# 1_P1.net
KiCad netlist of a schematic drawn in Altium Designer
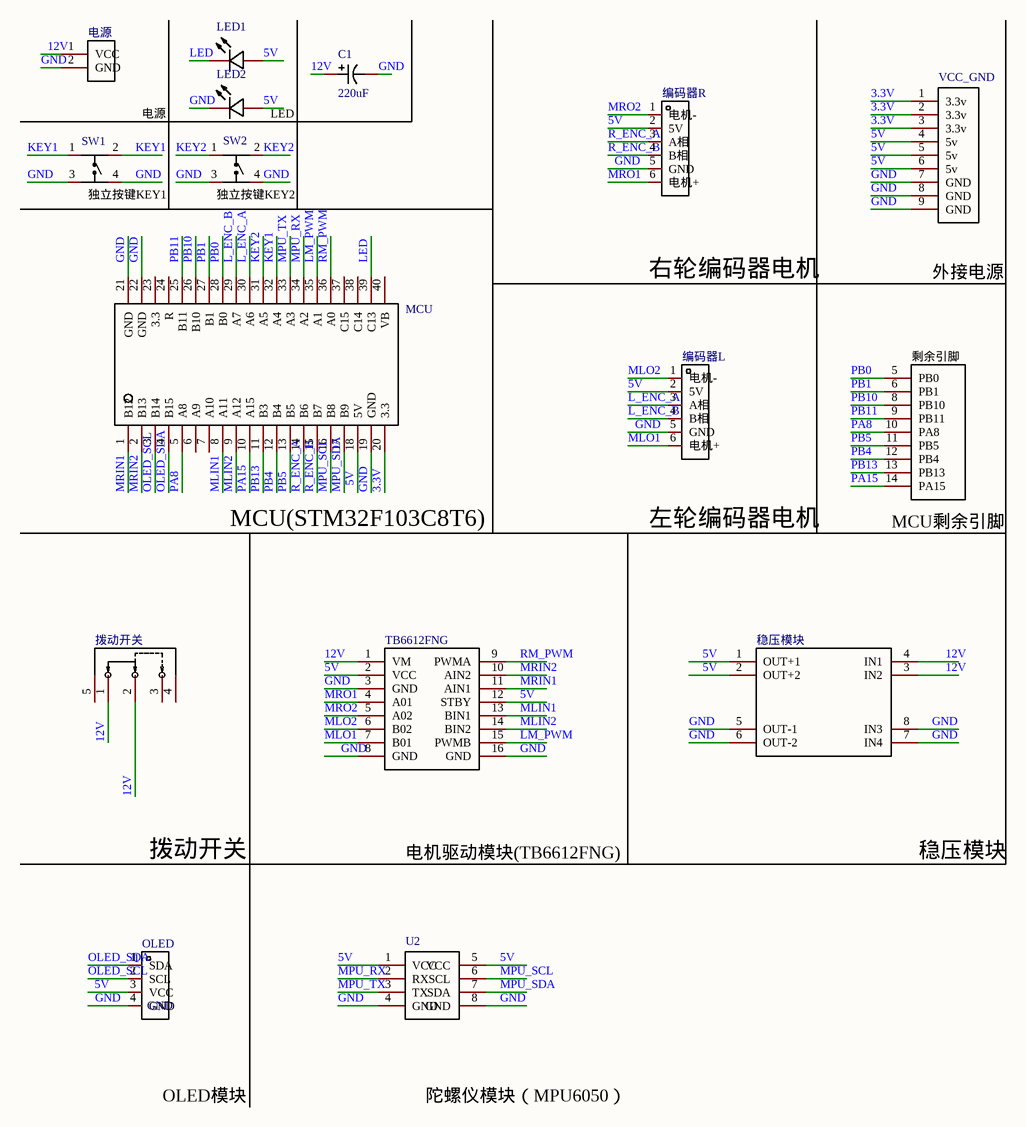
[diagram p0: 1_P1.schdoc]

(export (version "E")
  (design (tool "Eeschema 10.0.6"))
  (components
    (comp (ref "C1")
      (value "220uF")
      (description "容值:220uF;额定电压:25V;电容体直径:-;电容体长度:-;脚间距:3.5mm;纹波电流:-;等效串联电阻:-;工作寿命:-;")
      (fields (field (name "MANUFACTURER") "PANASONIC(松下)") (field (name "MANUFACTURER PART") "EEUFM1E221"))
      (libsource (lib "altium-import") (part "root_0_U1_"))
    )
    (comp (ref "LED1")
      (value "HL-PST-1608U51GC")
      (description "发光颜色:翠绿;透镜颜色:无色透明;主波长:-;色温:-;测试电流:10mA;功率:66mW;发光角度:130°;安装方式:正贴;工作温度:-40~+85;")
      (fields (field (name "MANUFACTURER") "HONGLITRONIC(鸿利光电)"))
      (libsource (lib "altium-import") (part "root_0_HL-PST-1608U51GC_"))
    )
    (comp (ref "LED2")
      (value "HL-PST-1608U51GC")
      (description "发光颜色:翠绿;透镜颜色:无色透明;主波长:-;色温:-;测试电流:10mA;功率:66mW;发光角度:130°;安装方式:正贴;工作温度:-40~+85;")
      (fields (field (name "MANUFACTURER") "HONGLITRONIC(鸿利光电)"))
      (libsource (lib "altium-import") (part "root_0_HL-PST-1608U51GC_"))
    )
    (comp (ref "MCU")
      (value "Stm32f103c8t6")
      (description "模块")
      (libsource (lib "altium-import") (part "root_1_Stm32f103c8t6_"))
    )
    (comp (ref "OLED")
      (value "OLED（4Pin）")
      (fields (field (name "NAME") "GND") (field (name "NUMBER") "1"))
      (libsource (lib "altium-import") (part "root_0_OLED（4Pin）_"))
    )
    (comp (ref "SW1")
      (value "KH-6X6X5H-TJ")
      (fields (field (name "MANUFACTURER") "kinghelm(金航标)"))
      (libsource (lib "altium-import") (part "root_0_KH-6X6X5H-TJ_"))
    )
    (comp (ref "SW2")
      (value "KH-6X6X5H-TJ")
      (fields (field (name "MANUFACTURER") "kinghelm(金航标)"))
      (libsource (lib "altium-import") (part "root_0_KH-6X6X5H-TJ_"))
    )
    (comp (ref "TB6612FNG")
      (value "TB6612fng（16PIN）")
      (libsource (lib "altium-import") (part "root_0_TB6612fng（16PIN）_"))
    )
    (comp (ref "U1") (value "MCU剩余引脚") (libsource (lib "altium-import") (part "root_0_MCU剩余引脚_")))
    (comp (ref "U2") (value "MPU6050_JY-61") (libsource (lib "altium-import") (part "root_0_MPU6050_JY-61_")))
    (comp (ref "VCC_GND") (value "VCC_GND") (libsource (lib "altium-import") (part "root_0_VCC_GND_")))
    (comp (ref "拨动开关")
      (value "拨动开关（3PIN）")
      (fields (field (name "MANUFACTURER") "SHOU HAN(首韩)") (field (name "MANUFACTURER PART") "SK12D07VG4"))
      (libsource (lib "altium-import") (part "root_0_拨动开关（3PIN）_"))
    )
    (comp (ref "电源") (value "电源") (libsource (lib "altium-import") (part "root_0_电源_")))
    (comp (ref "稳压模块")
      (value "稳压模块（-5v）")
      (description "模块")
      (libsource (lib "altium-import") (part "root_0_稳压模块（-5v）_"))
    )
    (comp (ref "编码器L")
      (value "A2547WR-6P")
      (description "参考系列:-;间距:2.54mm;插针结构:1x6P;排数:1;每排PIN数:6;行距:-;安装方式:-;触头材质:黄铜;")
      (fields (field (name "MANUFACTURER") "CJT(长江连接器)"))
      (libsource (lib "altium-import") (part "root_0_A2547WR-6P_"))
    )
    (comp (ref "编码器R")
      (value "A2547WR-6P")
      (description "参考系列:-;间距:2.54mm;插针结构:1x6P;排数:1;每排PIN数:6;行距:-;安装方式:-;触头材质:黄铜;")
      (fields (field (name "MANUFACTURER") "CJT(长江连接器)"))
      (libsource (lib "altium-import") (part "root_0_A2547WR-6P_"))
    )
  )
  (nets
    (net (code "1") (name "/3.3V") (class "Default")
      (node (ref "MCU") (pin "20") (pinfunction "3.3_20") (pintype "passive"))
      (node (ref "VCC_GND") (pin "1") (pinfunction "3.3v_1") (pintype "passive"))
      (node (ref "VCC_GND") (pin "2") (pinfunction "3.3v_2") (pintype "passive"))
      (node (ref "VCC_GND") (pin "3") (pinfunction "3.3v_3") (pintype "passive"))
    )
    (net (code "2") (name "/5V") (class "Default")
      (node (ref "LED1") (pin "1") (pinfunction "A_1") (pintype "passive"))
      (node (ref "LED2") (pin "1") (pinfunction "A_1") (pintype "passive"))
      (node (ref "MCU") (pin "18") (pinfunction "5V_18") (pintype "passive"))
      (node (ref "OLED") (pin "3") (pinfunction "VCC_3") (pintype "passive"))
      (node (ref "TB6612FNG") (pin "12") (pinfunction "STBY_12") (pintype "passive"))
      (node (ref "TB6612FNG") (pin "2") (pinfunction "VCC_2") (pintype "passive"))
      (node (ref "U2") (pin "1") (pinfunction "VCC_1") (pintype "passive"))
      (node (ref "U2") (pin "5") (pinfunction "VCC_5") (pintype "passive"))
      (node (ref "VCC_GND") (pin "4") (pinfunction "5v_4") (pintype "passive"))
      (node (ref "VCC_GND") (pin "5") (pinfunction "5v_5") (pintype "passive"))
      (node (ref "VCC_GND") (pin "6") (pinfunction "5v_6") (pintype "passive"))
      (node (ref "稳压模块") (pin "1") (pinfunction "OUT+1_1") (pintype "passive"))
      (node (ref "稳压模块") (pin "2") (pinfunction "OUT+2_2") (pintype "passive"))
      (node (ref "编码器L") (pin "2") (pinfunction "5V_2") (pintype "passive"))
      (node (ref "编码器R") (pin "2") (pinfunction "5V_2") (pintype "passive"))
    )
    (net (code "3") (name "/12V") (class "Default")
      (node (ref "C1") (pin "1") (pinfunction "1_1") (pintype "passive"))
      (node (ref "TB6612FNG") (pin "1") (pinfunction "VM_1") (pintype "passive"))
      (node (ref "拨动开关") (pin "1") (pinfunction "1_1") (pintype "passive"))
      (node (ref "拨动开关") (pin "2") (pinfunction "2_2") (pintype "passive"))
      (node (ref "电源") (pin "1") (pinfunction "VCC_1") (pintype "passive"))
      (node (ref "稳压模块") (pin "3") (pinfunction "IN2_3") (pintype "passive"))
      (node (ref "稳压模块") (pin "4") (pinfunction "IN1_4") (pintype "passive"))
    )
    (net (code "5") (name "/GND") (class "Default")
      (node (ref "C1") (pin "2") (pinfunction "2_2") (pintype "passive"))
      (node (ref "LED2") (pin "2") (pinfunction "K_2") (pintype "passive"))
      (node (ref "MCU") (pin "19") (pinfunction "GND_19") (pintype "passive"))
      (node (ref "MCU") (pin "21") (pinfunction "GND_21") (pintype "passive"))
      (node (ref "MCU") (pin "22") (pinfunction "GND_22") (pintype "passive"))
      (node (ref "OLED") (pin "4") (pinfunction "GND_4") (pintype "passive"))
      (node (ref "SW1") (pin "3") (pinfunction "3_3") (pintype "passive"))
      (node (ref "SW1") (pin "4") (pinfunction "4_4") (pintype "passive"))
      (node (ref "SW2") (pin "3") (pinfunction "3_3") (pintype "passive"))
      (node (ref "SW2") (pin "4") (pinfunction "4_4") (pintype "passive"))
      (node (ref "TB6612FNG") (pin "16") (pinfunction "GND_16") (pintype "passive"))
      (node (ref "TB6612FNG") (pin "3") (pinfunction "GND_3") (pintype "passive"))
      (node (ref "TB6612FNG") (pin "8") (pinfunction "GND_8") (pintype "passive"))
      (node (ref "U2") (pin "4") (pinfunction "GND_4") (pintype "passive"))
      (node (ref "U2") (pin "8") (pinfunction "GND_8") (pintype "passive"))
      (node (ref "VCC_GND") (pin "7") (pinfunction "GND_7") (pintype "passive"))
      (node (ref "VCC_GND") (pin "8") (pinfunction "GND_8") (pintype "passive"))
      (node (ref "VCC_GND") (pin "9") (pinfunction "GND_9") (pintype "passive"))
      (node (ref "电源") (pin "2") (pinfunction "GND_2") (pintype "passive"))
      (node (ref "稳压模块") (pin "5") (pinfunction "OUT-1_5") (pintype "passive"))
      (node (ref "稳压模块") (pin "6") (pinfunction "OUT-2_6") (pintype "passive"))
      (node (ref "稳压模块") (pin "7") (pinfunction "IN4_7") (pintype "passive"))
      (node (ref "稳压模块") (pin "8") (pinfunction "IN3_8") (pintype "passive"))
      (node (ref "编码器L") (pin "5") (pinfunction "GND_5") (pintype "passive"))
      (node (ref "编码器R") (pin "5") (pinfunction "GND_5") (pintype "passive"))
    )
    (net (code "6") (name "/KEY1") (class "Default")
      (node (ref "MCU") (pin "32") (pinfunction "A4_32") (pintype "passive"))
      (node (ref "SW1") (pin "1") (pinfunction "1_1") (pintype "passive"))
      (node (ref "SW1") (pin "2") (pinfunction "2_2") (pintype "passive"))
    )
    (net (code "7") (name "/KEY2") (class "Default")
      (node (ref "MCU") (pin "31") (pinfunction "A5_31") (pintype "passive"))
      (node (ref "SW2") (pin "1") (pinfunction "1_1") (pintype "passive"))
      (node (ref "SW2") (pin "2") (pinfunction "2_2") (pintype "passive"))
    )
    (net (code "8") (name "/LED") (class "Default")
      (node (ref "LED1") (pin "2") (pinfunction "K_2") (pintype "passive"))
      (node (ref "MCU") (pin "39") (pinfunction "C13_39") (pintype "passive"))
    )
    (net (code "9") (name "/LM_PWM") (class "Default")
      (node (ref "MCU") (pin "35") (pinfunction "A1_35") (pintype "passive"))
      (node (ref "TB6612FNG") (pin "15") (pinfunction "PWMB_15") (pintype "passive"))
    )
    (net (code "10") (name "/L_ENC_A") (class "Default")
      (node (ref "MCU") (pin "30") (pinfunction "A6_30") (pintype "passive"))
      (node (ref "编码器L") (pin "3") (pinfunction "A相_3") (pintype "passive"))
    )
    (net (code "11") (name "/L_ENC_B") (class "Default")
      (node (ref "MCU") (pin "29") (pinfunction "A7_29") (pintype "passive"))
      (node (ref "编码器L") (pin "4") (pinfunction "B相_4") (pintype "passive"))
    )
    (net (code "12") (name "/MLIN1") (class "Default")
      (node (ref "MCU") (pin "8") (pinfunction "A11_8") (pintype "passive"))
      (node (ref "TB6612FNG") (pin "13") (pinfunction "BIN1_13") (pintype "passive"))
    )
    (net (code "13") (name "/MLIN2") (class "Default")
      (node (ref "MCU") (pin "9") (pinfunction "A12_9") (pintype "passive"))
      (node (ref "TB6612FNG") (pin "14") (pinfunction "BIN2_14") (pintype "passive"))
    )
    (net (code "14") (name "/MLO1") (class "Default")
      (node (ref "TB6612FNG") (pin "7") (pinfunction "B01_7") (pintype "passive"))
      (node (ref "编码器L") (pin "6") (pinfunction "电机+_6") (pintype "passive"))
    )
    (net (code "15") (name "/MLO2") (class "Default")
      (node (ref "TB6612FNG") (pin "6") (pinfunction "B02_6") (pintype "passive"))
      (node (ref "编码器L") (pin "1") (pinfunction "电机-_1") (pintype "passive"))
    )
    (net (code "16") (name "/MPU_RX") (class "Default")
      (node (ref "MCU") (pin "34") (pinfunction "A2_34") (pintype "passive"))
      (node (ref "U2") (pin "2") (pinfunction "RX_2") (pintype "passive"))
    )
    (net (code "17") (name "/MPU_SCL") (class "Default")
      (node (ref "MCU") (pin "16") (pinfunction "B8_16") (pintype "passive"))
      (node (ref "U2") (pin "6") (pinfunction "SCL_6") (pintype "passive"))
    )
    (net (code "18") (name "/MPU_SDA") (class "Default")
      (node (ref "MCU") (pin "17") (pinfunction "B9_17") (pintype "passive"))
      (node (ref "U2") (pin "7") (pinfunction "SDA_7") (pintype "passive"))
    )
    (net (code "19") (name "/MPU_TX") (class "Default")
      (node (ref "MCU") (pin "33") (pinfunction "A3_33") (pintype "passive"))
      (node (ref "U2") (pin "3") (pinfunction "TX_3") (pintype "passive"))
    )
    (net (code "20") (name "/MRIN1") (class "Default")
      (node (ref "MCU") (pin "1") (pinfunction "B12_1") (pintype "passive"))
      (node (ref "TB6612FNG") (pin "11") (pinfunction "AIN1_11") (pintype "passive"))
    )
    (net (code "21") (name "/MRIN2") (class "Default")
      (node (ref "MCU") (pin "2") (pinfunction "B13_2") (pintype "passive"))
      (node (ref "TB6612FNG") (pin "10") (pinfunction "AIN2_10") (pintype "passive"))
    )
    (net (code "22") (name "/MRO1") (class "Default")
      (node (ref "TB6612FNG") (pin "4") (pinfunction "A01_4") (pintype "passive"))
      (node (ref "编码器R") (pin "6") (pinfunction "电机+_6") (pintype "passive"))
    )
    (net (code "23") (name "/MRO2") (class "Default")
      (node (ref "TB6612FNG") (pin "5") (pinfunction "A02_5") (pintype "passive"))
      (node (ref "编码器R") (pin "1") (pinfunction "电机-_1") (pintype "passive"))
    )
    (net (code "24") (name "/OLED_SCL") (class "Default")
      (node (ref "MCU") (pin "3") (pinfunction "B14_3") (pintype "passive"))
      (node (ref "OLED") (pin "2") (pinfunction "SCL_2") (pintype "passive"))
    )
    (net (code "25") (name "/OLED_SDA") (class "Default")
      (node (ref "MCU") (pin "4") (pinfunction "B15_4") (pintype "passive"))
      (node (ref "OLED") (pin "1") (pinfunction "SDA_1") (pintype "passive"))
    )
    (net (code "26") (name "/PA8") (class "Default")
      (node (ref "MCU") (pin "5") (pinfunction "A8_5") (pintype "passive"))
      (node (ref "U1") (pin "10") (pinfunction "PA8_10") (pintype "passive"))
    )
    (net (code "27") (name "/PA15") (class "Default")
      (node (ref "MCU") (pin "10") (pinfunction "A15_10") (pintype "passive"))
      (node (ref "U1") (pin "14") (pinfunction "PA15_14") (pintype "passive"))
    )
    (net (code "28") (name "/PB0") (class "Default")
      (node (ref "MCU") (pin "28") (pinfunction "B0_28") (pintype "passive"))
      (node (ref "U1") (pin "5") (pinfunction "PB0_5") (pintype "passive"))
    )
    (net (code "29") (name "/PB1") (class "Default")
      (node (ref "MCU") (pin "27") (pinfunction "B1_27") (pintype "passive"))
      (node (ref "U1") (pin "6") (pinfunction "PB1_6") (pintype "passive"))
    )
    (net (code "30") (name "/PB4") (class "Default")
      (node (ref "MCU") (pin "12") (pinfunction "B4_12") (pintype "passive"))
      (node (ref "U1") (pin "12") (pinfunction "PB4_12") (pintype "passive"))
    )
    (net (code "31") (name "/PB5") (class "Default")
      (node (ref "MCU") (pin "13") (pinfunction "B5_13") (pintype "passive"))
      (node (ref "U1") (pin "11") (pinfunction "PB5_11") (pintype "passive"))
    )
    (net (code "32") (name "/PB10") (class "Default")
      (node (ref "MCU") (pin "26") (pinfunction "B10_26") (pintype "passive"))
      (node (ref "U1") (pin "8") (pinfunction "PB10_8") (pintype "passive"))
    )
    (net (code "33") (name "/PB11") (class "Default")
      (node (ref "MCU") (pin "25") (pinfunction "B11_25") (pintype "passive"))
      (node (ref "U1") (pin "9") (pinfunction "PB11_9") (pintype "passive"))
    )
    (net (code "34") (name "/PB13") (class "Default")
      (node (ref "MCU") (pin "11") (pinfunction "B3_11") (pintype "passive"))
      (node (ref "U1") (pin "13") (pinfunction "PB13_13") (pintype "passive"))
    )
    (net (code "35") (name "/RM_PWM") (class "Default")
      (node (ref "MCU") (pin "36") (pinfunction "A0_36") (pintype "passive"))
      (node (ref "TB6612FNG") (pin "9") (pinfunction "PWMA_9") (pintype "passive"))
    )
    (net (code "36") (name "/R_ENC_A") (class "Default")
      (node (ref "MCU") (pin "14") (pinfunction "B6_14") (pintype "passive"))
      (node (ref "编码器R") (pin "3") (pinfunction "A相_3") (pintype "passive"))
    )
    (net (code "37") (name "/R_ENC_B") (class "Default")
      (node (ref "MCU") (pin "15") (pinfunction "B7_15") (pintype "passive"))
      (node (ref "编码器R") (pin "4") (pinfunction "B相_4") (pintype "passive"))
    )
    (net (code "38") (name "unconnected-(MCU-3.3-Pad23)") (class "Default")
      (node (ref "MCU") (pin "23") (pinfunction "3.3_23") (pintype "passive"))
    )
    (net (code "39") (name "unconnected-(MCU-A9-Pad6)") (class "Default")
      (node (ref "MCU") (pin "6") (pinfunction "A9_6") (pintype "passive"))
    )
    (net (code "40") (name "unconnected-(MCU-A10-Pad7)") (class "Default")
      (node (ref "MCU") (pin "7") (pinfunction "A10_7") (pintype "passive"))
    )
    (net (code "41") (name "unconnected-(MCU-C14-Pad38)") (class "Default")
      (node (ref "MCU") (pin "38") (pinfunction "C14_38") (pintype "passive"))
    )
    (net (code "42") (name "unconnected-(MCU-C15-Pad37)") (class "Default")
      (node (ref "MCU") (pin "37") (pinfunction "C15_37") (pintype "passive"))
    )
    (net (code "43") (name "unconnected-(MCU-R-Pad24)") (class "Default")
      (node (ref "MCU") (pin "24") (pinfunction "R_24") (pintype "passive"))
    )
    (net (code "44") (name "unconnected-(MCU-VB-Pad40)") (class "Default")
      (node (ref "MCU") (pin "40") (pinfunction "VB_40") (pintype "passive"))
    )
    (net (code "45") (name "unconnected-(拨动开关-Pad3)") (class "Default")
      (node (ref "拨动开关") (pin "3") (pinfunction "3_3") (pintype "passive"))
    )
    (net (code "46") (name "unconnected-(拨动开关-Pad4)") (class "Default")
      (node (ref "拨动开关") (pin "4") (pinfunction "4_4") (pintype "passive"))
    )
    (net (code "47") (name "unconnected-(拨动开关-Pad5)") (class "Default")
      (node (ref "拨动开关") (pin "5") (pinfunction "5_5") (pintype "passive"))
    )
  )
)
